# connector.net
KiCad netlist of a schematic drawn in Altium Designer
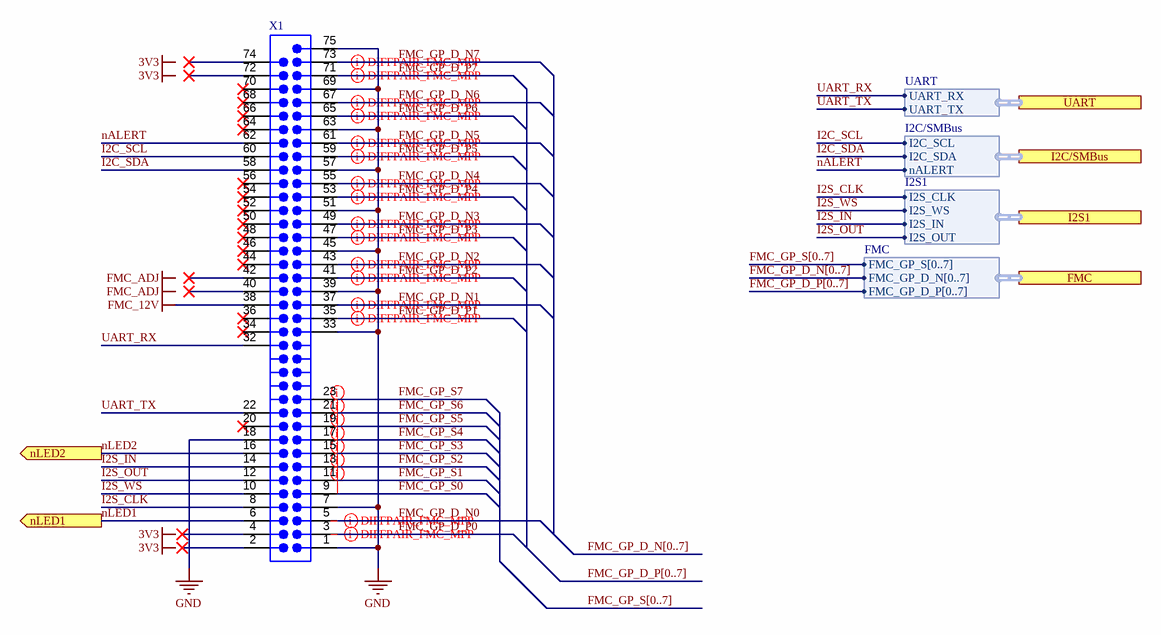
[diagram p0: connector.SchDoc]

(export (version "E")
  (design (tool "Eeschema 10.0.6"))
  (components
    (comp (ref "X1")
      (value "CONN PWR CARD EDGE PCB SLOT MALE")
      (footprint "CON-67_0.5MM_PCB_SLOT")
      (description "Mates with 2199119-4 - No BOM")
      (libsource (lib "ETHZ Vault") (part "CON-67_0.5mm_PCB_SLOT"))
    )
  )
  (nets
    (net (code "5") (name "/FMC_GP_D_N0") (class "Default")
      (node (ref "X1") (pin "5") (pinfunction "5_5") (pintype "passive"))
    )
    (net (code "6") (name "/FMC_GP_D_N1") (class "Default")
      (node (ref "X1") (pin "37") (pinfunction "37_37") (pintype "passive"))
    )
    (net (code "7") (name "/FMC_GP_D_N2") (class "Default")
      (node (ref "X1") (pin "43") (pinfunction "43_43") (pintype "passive"))
    )
    (net (code "8") (name "/FMC_GP_D_N3") (class "Default")
      (node (ref "X1") (pin "49") (pinfunction "49_49") (pintype "passive"))
    )
    (net (code "9") (name "/FMC_GP_D_N4") (class "Default")
      (node (ref "X1") (pin "55") (pinfunction "55_55") (pintype "passive"))
    )
    (net (code "10") (name "/FMC_GP_D_N5") (class "Default")
      (node (ref "X1") (pin "61") (pinfunction "61_61") (pintype "passive"))
    )
    (net (code "11") (name "/FMC_GP_D_N6") (class "Default")
      (node (ref "X1") (pin "67") (pinfunction "67_67") (pintype "passive"))
    )
    (net (code "12") (name "/FMC_GP_D_N7") (class "Default")
      (node (ref "X1") (pin "73") (pinfunction "73_73") (pintype "passive"))
    )
    (net (code "14") (name "/FMC_GP_D_P0") (class "Default")
      (node (ref "X1") (pin "3") (pinfunction "3_3") (pintype "passive"))
    )
    (net (code "15") (name "/FMC_GP_D_P1") (class "Default")
      (node (ref "X1") (pin "35") (pinfunction "35_35") (pintype "passive"))
    )
    (net (code "16") (name "/FMC_GP_D_P2") (class "Default")
      (node (ref "X1") (pin "41") (pinfunction "41_41") (pintype "passive"))
    )
    (net (code "17") (name "/FMC_GP_D_P3") (class "Default")
      (node (ref "X1") (pin "47") (pinfunction "47_47") (pintype "passive"))
    )
    (net (code "18") (name "/FMC_GP_D_P4") (class "Default")
      (node (ref "X1") (pin "53") (pinfunction "53_53") (pintype "passive"))
    )
    (net (code "19") (name "/FMC_GP_D_P5") (class "Default")
      (node (ref "X1") (pin "59") (pinfunction "59_59") (pintype "passive"))
    )
    (net (code "20") (name "/FMC_GP_D_P6") (class "Default")
      (node (ref "X1") (pin "65") (pinfunction "65_65") (pintype "passive"))
    )
    (net (code "21") (name "/FMC_GP_D_P7") (class "Default")
      (node (ref "X1") (pin "71") (pinfunction "71_71") (pintype "passive"))
    )
    (net (code "23") (name "/FMC_GP_S0") (class "Default")
      (node (ref "X1") (pin "9") (pinfunction "9_9") (pintype "passive"))
    )
    (net (code "24") (name "/FMC_GP_S1") (class "Default")
      (node (ref "X1") (pin "11") (pinfunction "11_11") (pintype "passive"))
    )
    (net (code "25") (name "/FMC_GP_S2") (class "Default")
      (node (ref "X1") (pin "13") (pinfunction "13_13") (pintype "passive"))
    )
    (net (code "26") (name "/FMC_GP_S3") (class "Default")
      (node (ref "X1") (pin "15") (pinfunction "15_15") (pintype "passive"))
    )
    (net (code "27") (name "/FMC_GP_S4") (class "Default")
      (node (ref "X1") (pin "17") (pinfunction "17_17") (pintype "passive"))
    )
    (net (code "28") (name "/FMC_GP_S5") (class "Default")
      (node (ref "X1") (pin "19") (pinfunction "19_19") (pintype "passive"))
    )
    (net (code "29") (name "/FMC_GP_S6") (class "Default")
      (node (ref "X1") (pin "21") (pinfunction "21_21") (pintype "passive"))
    )
    (net (code "30") (name "/FMC_GP_S7") (class "Default")
      (node (ref "X1") (pin "23") (pinfunction "23_23") (pintype "passive"))
    )
    (net (code "32") (name "/I2C_SCL") (class "Default")
      (node (ref "X1") (pin "60") (pinfunction "55_60") (pintype "passive"))
    )
    (net (code "33") (name "/I2C_SDA") (class "Default")
      (node (ref "X1") (pin "58") (pinfunction "54_58") (pintype "passive"))
    )
    (net (code "34") (name "/I2S_CLK") (class "Default")
      (node (ref "X1") (pin "8") (pinfunction "8_8") (pintype "passive"))
    )
    (net (code "35") (name "/I2S_IN") (class "Default")
      (node (ref "X1") (pin "14") (pinfunction "14_14") (pintype "passive"))
    )
    (net (code "36") (name "/I2S_OUT") (class "Default")
      (node (ref "X1") (pin "12") (pinfunction "12_12") (pintype "passive"))
    )
    (net (code "37") (name "/I2S_WS") (class "Default")
      (node (ref "X1") (pin "10") (pinfunction "10_10") (pintype "passive"))
    )
    (net (code "38") (name "/UART_RX") (class "Default")
      (node (ref "X1") (pin "32") (pinfunction "32_32") (pintype "passive"))
    )
    (net (code "39") (name "/UART_TX") (class "Default")
      (node (ref "X1") (pin "22") (pinfunction "22_22") (pintype "passive"))
    )
    (net (code "40") (name "/nALERT") (class "Default")
      (node (ref "X1") (pin "62") (pinfunction "62_62") (pintype "passive"))
    )
    (net (code "41") (name "/nLED1") (class "Default")
      (node (ref "X1") (pin "6") (pinfunction "6_6") (pintype "passive"))
    )
    (net (code "42") (name "/nLED2") (class "Default")
      (node (ref "X1") (pin "16") (pinfunction "16_16") (pintype "passive"))
    )
    (net (code "48") (name "FMC_12V") (class "Default")
      (node (ref "X1") (pin "38") (pinfunction "38_38") (pintype "passive"))
    )
    (net (code "50") (name "GND") (class "Default")
      (node (ref "X1") (pin "1") (pinfunction "1_1") (pintype "passive"))
      (node (ref "X1") (pin "18") (pinfunction "18_18") (pintype "passive"))
      (node (ref "X1") (pin "33") (pinfunction "33_33") (pintype "passive"))
      (node (ref "X1") (pin "39") (pinfunction "39_39") (pintype "passive"))
      (node (ref "X1") (pin "45") (pinfunction "45_45") (pintype "passive"))
      (node (ref "X1") (pin "51") (pinfunction "51_51") (pintype "passive"))
      (node (ref "X1") (pin "57") (pinfunction "57_57") (pintype "passive"))
      (node (ref "X1") (pin "63") (pinfunction "63_63") (pintype "passive"))
      (node (ref "X1") (pin "69") (pinfunction "69_69") (pintype "passive"))
      (node (ref "X1") (pin "7") (pinfunction "7_7") (pintype "passive"))
      (node (ref "X1") (pin "75") (pinfunction "75_75") (pintype "passive"))
    )
    (net (code "51") (name "unconnected-(X1-51-Pad52)") (class "Default")
      (node (ref "X1") (pin "52") (pinfunction "51_52") (pintype "passive+no_connect"))
    )
    (net (code "52") (name "unconnected-(X1-52-Pad54)") (class "Default")
      (node (ref "X1") (pin "54") (pinfunction "52_54") (pintype "passive+no_connect"))
    )
    (net (code "53") (name "unconnected-(X1-53-Pad56)") (class "Default")
      (node (ref "X1") (pin "56") (pinfunction "53_56") (pintype "passive+no_connect"))
    )
    (net (code "54") (name "unconnected-(X1-Pad2)") (class "Default")
      (node (ref "X1") (pin "2") (pinfunction "2_2") (pintype "passive+no_connect"))
    )
    (net (code "55") (name "unconnected-(X1-Pad4)") (class "Default")
      (node (ref "X1") (pin "4") (pinfunction "4_4") (pintype "passive+no_connect"))
    )
    (net (code "56") (name "unconnected-(X1-Pad20)") (class "Default")
      (node (ref "X1") (pin "20") (pinfunction "20_20") (pintype "passive+no_connect"))
    )
    (net (code "57") (name "unconnected-(X1-Pad34)") (class "Default")
      (node (ref "X1") (pin "34") (pinfunction "34_34") (pintype "passive+no_connect"))
    )
    (net (code "58") (name "unconnected-(X1-Pad36)") (class "Default")
      (node (ref "X1") (pin "36") (pinfunction "36_36") (pintype "passive+no_connect"))
    )
    (net (code "59") (name "unconnected-(X1-Pad40)") (class "Default")
      (node (ref "X1") (pin "40") (pinfunction "40_40") (pintype "passive+no_connect"))
    )
    (net (code "60") (name "unconnected-(X1-Pad42)") (class "Default")
      (node (ref "X1") (pin "42") (pinfunction "42_42") (pintype "passive+no_connect"))
    )
    (net (code "61") (name "unconnected-(X1-Pad44)") (class "Default")
      (node (ref "X1") (pin "44") (pinfunction "44_44") (pintype "passive+no_connect"))
    )
    (net (code "62") (name "unconnected-(X1-Pad46)") (class "Default")
      (node (ref "X1") (pin "46") (pinfunction "46_46") (pintype "passive+no_connect"))
    )
    (net (code "63") (name "unconnected-(X1-Pad48)") (class "Default")
      (node (ref "X1") (pin "48") (pinfunction "48_48") (pintype "passive+no_connect"))
    )
    (net (code "64") (name "unconnected-(X1-Pad50)") (class "Default")
      (node (ref "X1") (pin "50") (pinfunction "50_50") (pintype "passive+no_connect"))
    )
    (net (code "65") (name "unconnected-(X1-Pad64)") (class "Default")
      (node (ref "X1") (pin "64") (pinfunction "64_64") (pintype "passive+no_connect"))
    )
    (net (code "66") (name "unconnected-(X1-Pad66)") (class "Default")
      (node (ref "X1") (pin "66") (pinfunction "66_66") (pintype "passive+no_connect"))
    )
    (net (code "67") (name "unconnected-(X1-Pad68)") (class "Default")
      (node (ref "X1") (pin "68") (pinfunction "68_68") (pintype "passive+no_connect"))
    )
    (net (code "68") (name "unconnected-(X1-Pad70)") (class "Default")
      (node (ref "X1") (pin "70") (pinfunction "70_70") (pintype "passive+no_connect"))
    )
    (net (code "69") (name "unconnected-(X1-Pad72)") (class "Default")
      (node (ref "X1") (pin "72") (pinfunction "72_72") (pintype "passive+no_connect"))
    )
    (net (code "70") (name "unconnected-(X1-Pad74)") (class "Default")
      (node (ref "X1") (pin "74") (pinfunction "74_74") (pintype "passive+no_connect"))
    )
  )
)
